# driver_VCC.net
KiCad netlist of a schematic drawn in Altium Designer
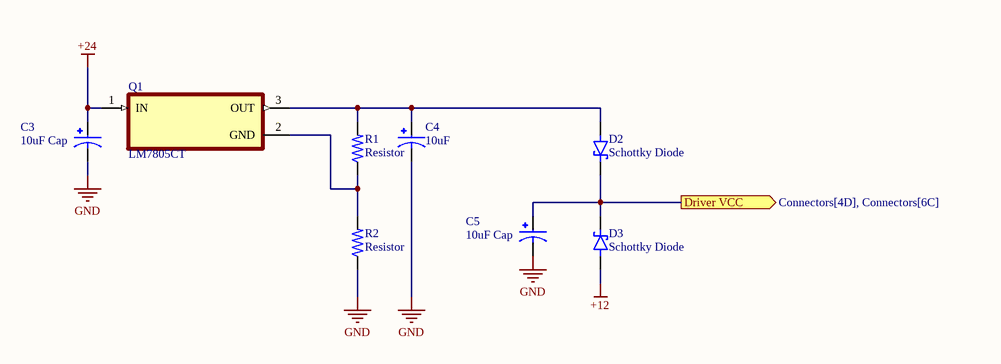
[diagram p0: driver VCC.SchDoc]

(export (version "E")
  (design (tool "Eeschema 10.0.6"))
  (components
    (comp (ref "C3")
      (value "10uF Cap")
      (footprint "CAP_10uF")
      (description "CAP ALUM 10UF 20% 50V RADIAL")
      (fields (field (name "MP") "ECE-A1HN100UI") (field (name "MF") "Panasonic"))
      (libsource (lib "MySCH_Library") (part "10uF Cap"))
    )
    (comp (ref "C4")
      (value "10uF")
      (footprint "CAP_10uF")
      (description "CAP ALUM 10UF 20% 50V RADIAL")
      (fields (field (name "MP") "ECE-A1HN100UI") (field (name "MF") "Panasonic"))
      (libsource (lib "MySCH_Library") (part "10uF Cap"))
    )
    (comp (ref "C5")
      (value "10uF Cap")
      (footprint "CAP_10uF")
      (description "CAP ALUM 10UF 20% 50V RADIAL")
      (fields (field (name "MP") "ECE-A1HN100UI") (field (name "MF") "Panasonic"))
      (libsource (lib "MySCH_Library") (part "10uF Cap"))
    )
    (comp (ref "D2")
      (value "Schottky Diode")
      (footprint "Common Trhough Hole")
      (fields (field (name "MF") "Diodes Inc.") (field (name "MP") "1N5817-T"))
      (libsource (lib "Diodes Through Hole") (part "Schottky Diode"))
    )
    (comp (ref "D3")
      (value "Schottky Diode")
      (footprint "Common Trhough Hole")
      (fields (field (name "MF") "Diodes Inc.") (field (name "MP") "1N5817-T"))
      (libsource (lib "Diodes Through Hole") (part "Schottky Diode"))
    )
    (comp (ref "Q1")
      (value "LM7805CT")
      (footprint "LM7805CT")
      (fields (field (name "MP") "LM7805CT/NOPB"))
      (libsource (lib "Voltage Regulators Through Hole") (part "LM7805CT"))
    )
    (comp (ref "R1")
      (value "Resistor")
      (footprint "Resistor_Through Hole")
      (fields
        (field (name "MP") "2-2176053-0")
        (field (name "TOLERANCE") "1%")
        (field (name "MF") "TE Connectivity")
      )
      (libsource (lib "Resistors Through Hole") (part "Resistor"))
    )
    (comp (ref "R2")
      (value "Resistor")
      (footprint "Resistor_Through Hole")
      (fields
        (field (name "MP") "2-2176053-0")
        (field (name "TOLERANCE") "1%")
        (field (name "MF") "TE Connectivity")
      )
      (libsource (lib "Resistors Through Hole") (part "Resistor"))
    )
  )
  (nets
    (net (code "1") (name "+12") (class "Default")
      (node (ref "D3") (pin "2") (pinfunction "A_2") (pintype "passive"))
    )
    (net (code "2") (name "+24") (class "Default")
      (node (ref "C3") (pin "P") (pinfunction "P_P") (pintype "passive"))
      (node (ref "Q1") (pin "1") (pinfunction "IN_1") (pintype "input"))
    )
    (net (code "3") (name "/Driver VCC") (class "Default")
      (node (ref "C5") (pin "P") (pinfunction "P_P") (pintype "passive"))
      (node (ref "D2") (pin "1") (pinfunction "K_1") (pintype "passive"))
      (node (ref "D3") (pin "1") (pinfunction "K_1") (pintype "passive"))
    )
    (net (code "4") (name "GND") (class "Default")
      (node (ref "C3") (pin "N") (pinfunction "N_N") (pintype "passive"))
      (node (ref "C4") (pin "N") (pinfunction "N_N") (pintype "passive"))
      (node (ref "C5") (pin "N") (pinfunction "N_N") (pintype "passive"))
      (node (ref "R2") (pin "1") (pinfunction "1_1") (pintype "passive"))
    )
    (net (code "5") (name "Net-(D2-A)") (class "Default")
      (node (ref "C4") (pin "P") (pinfunction "P_P") (pintype "passive"))
      (node (ref "D2") (pin "2") (pinfunction "A_2") (pintype "passive"))
      (node (ref "Q1") (pin "3") (pinfunction "OUT_3") (pintype "output"))
      (node (ref "R1") (pin "2") (pinfunction "2_2") (pintype "passive"))
    )
    (net (code "6") (name "Net-(Q1-GND)") (class "Default")
      (node (ref "Q1") (pin "2") (pinfunction "GND_2") (pintype "power_in"))
      (node (ref "R1") (pin "1") (pinfunction "1_1") (pintype "passive"))
      (node (ref "R2") (pin "2") (pinfunction "2_2") (pintype "passive"))
    )
  )
)
